# Bordnetzwandler.net
KiCad netlist of a schematic drawn in EAGLE
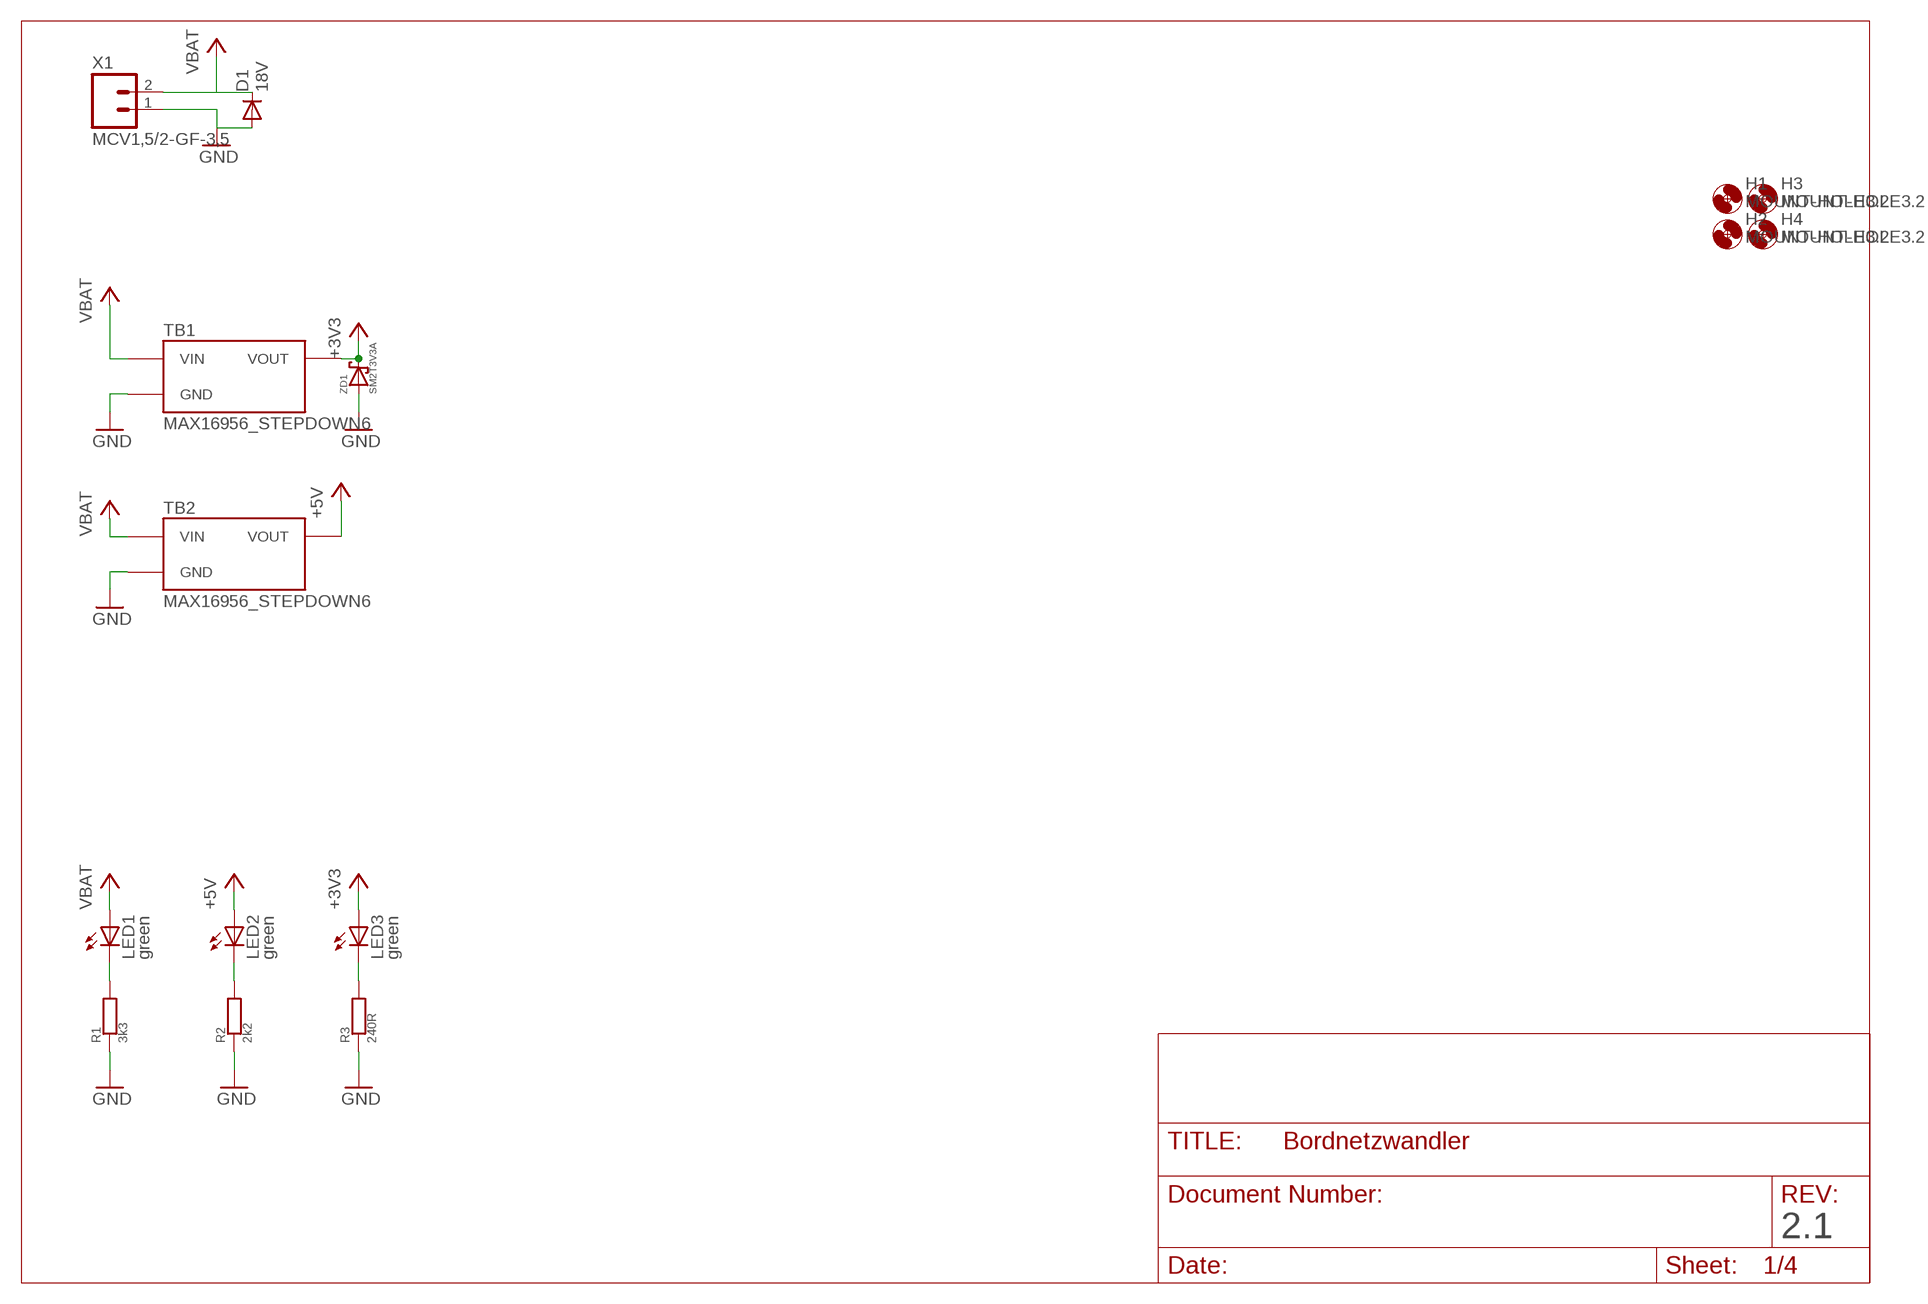
[diagram p0: schematic, sheet 1]
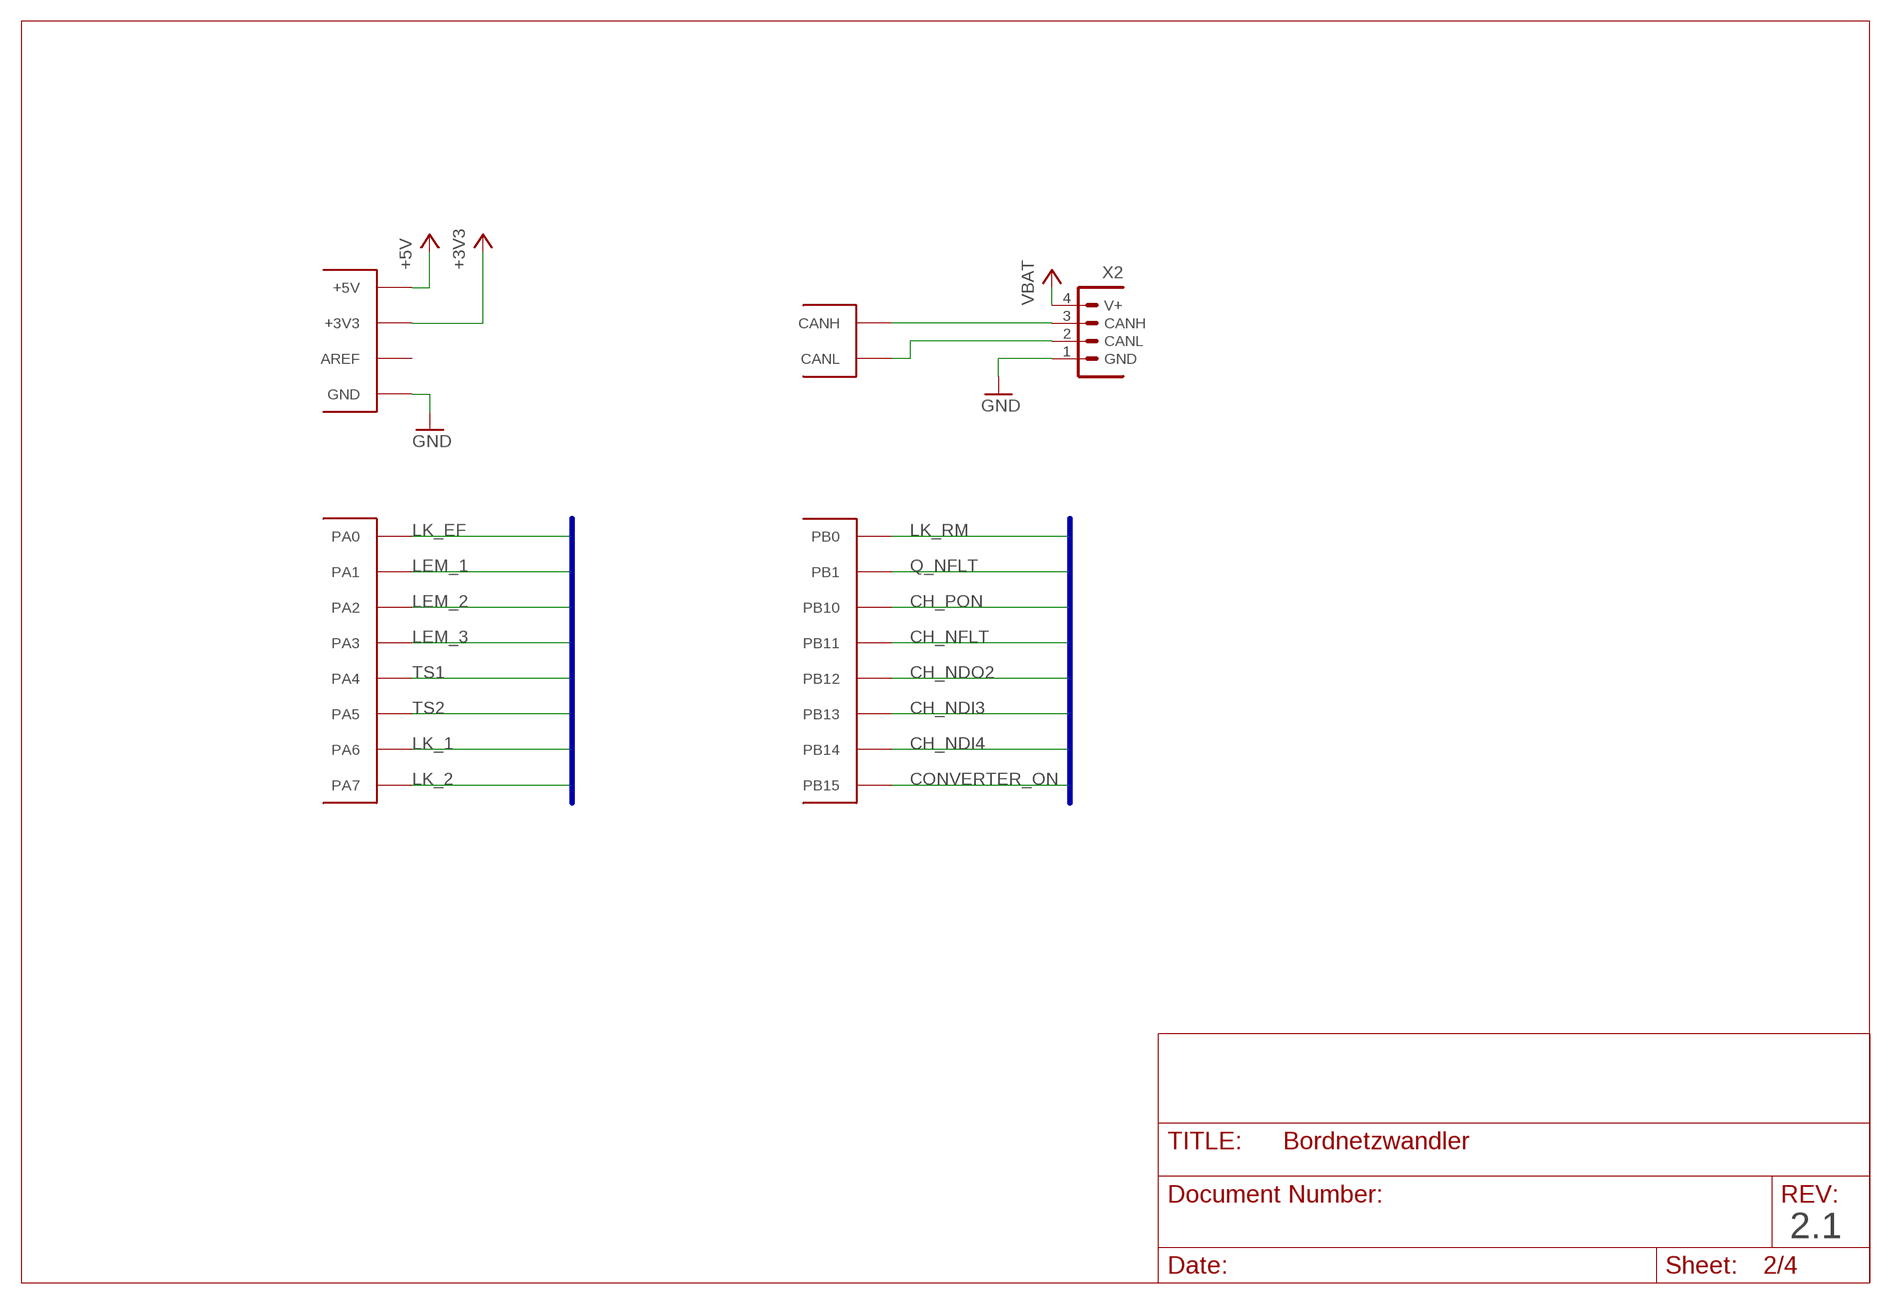
[diagram p1: schematic, sheet 2]
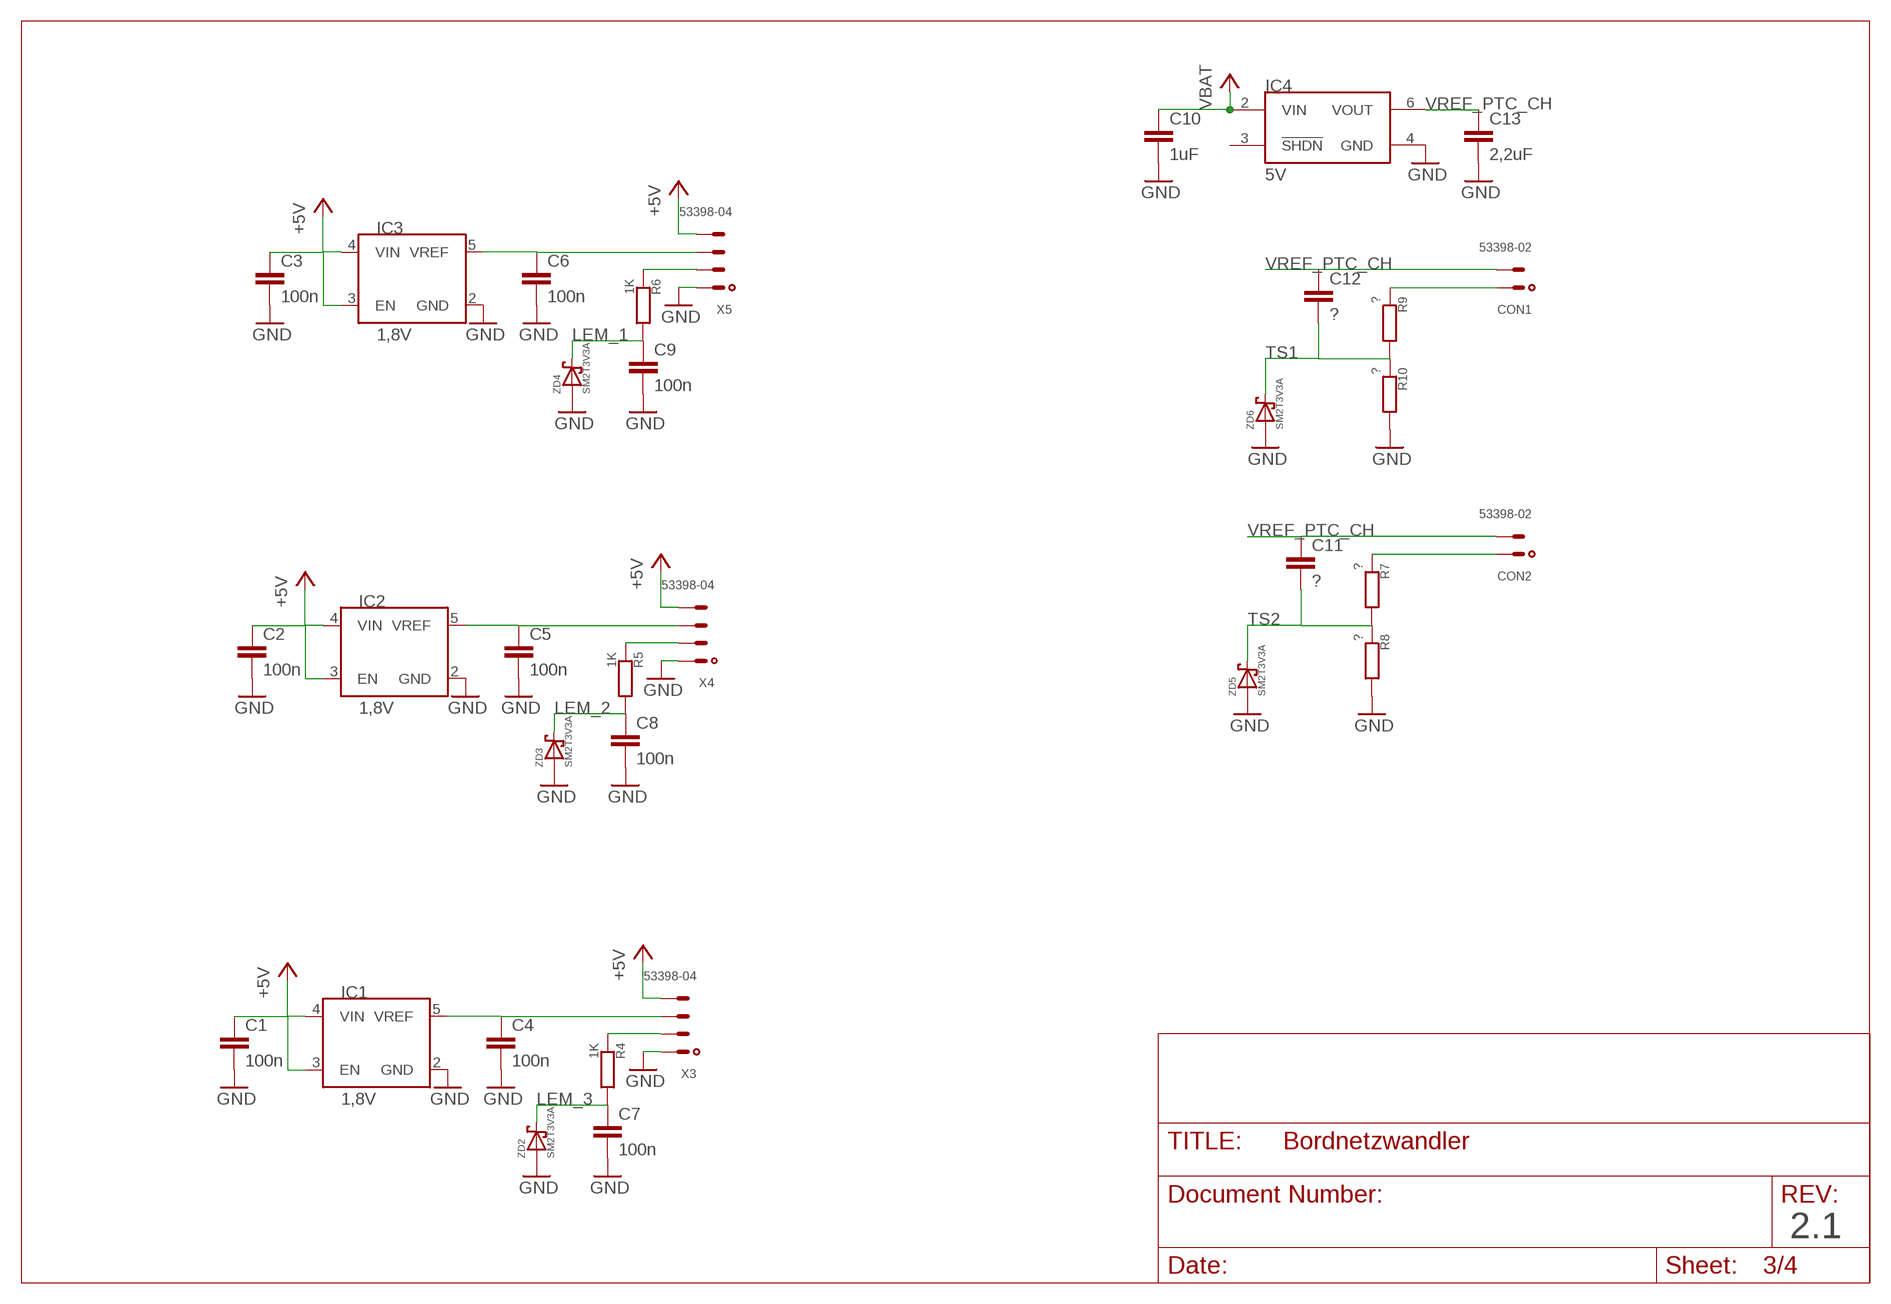
[diagram p2: schematic, sheet 3]
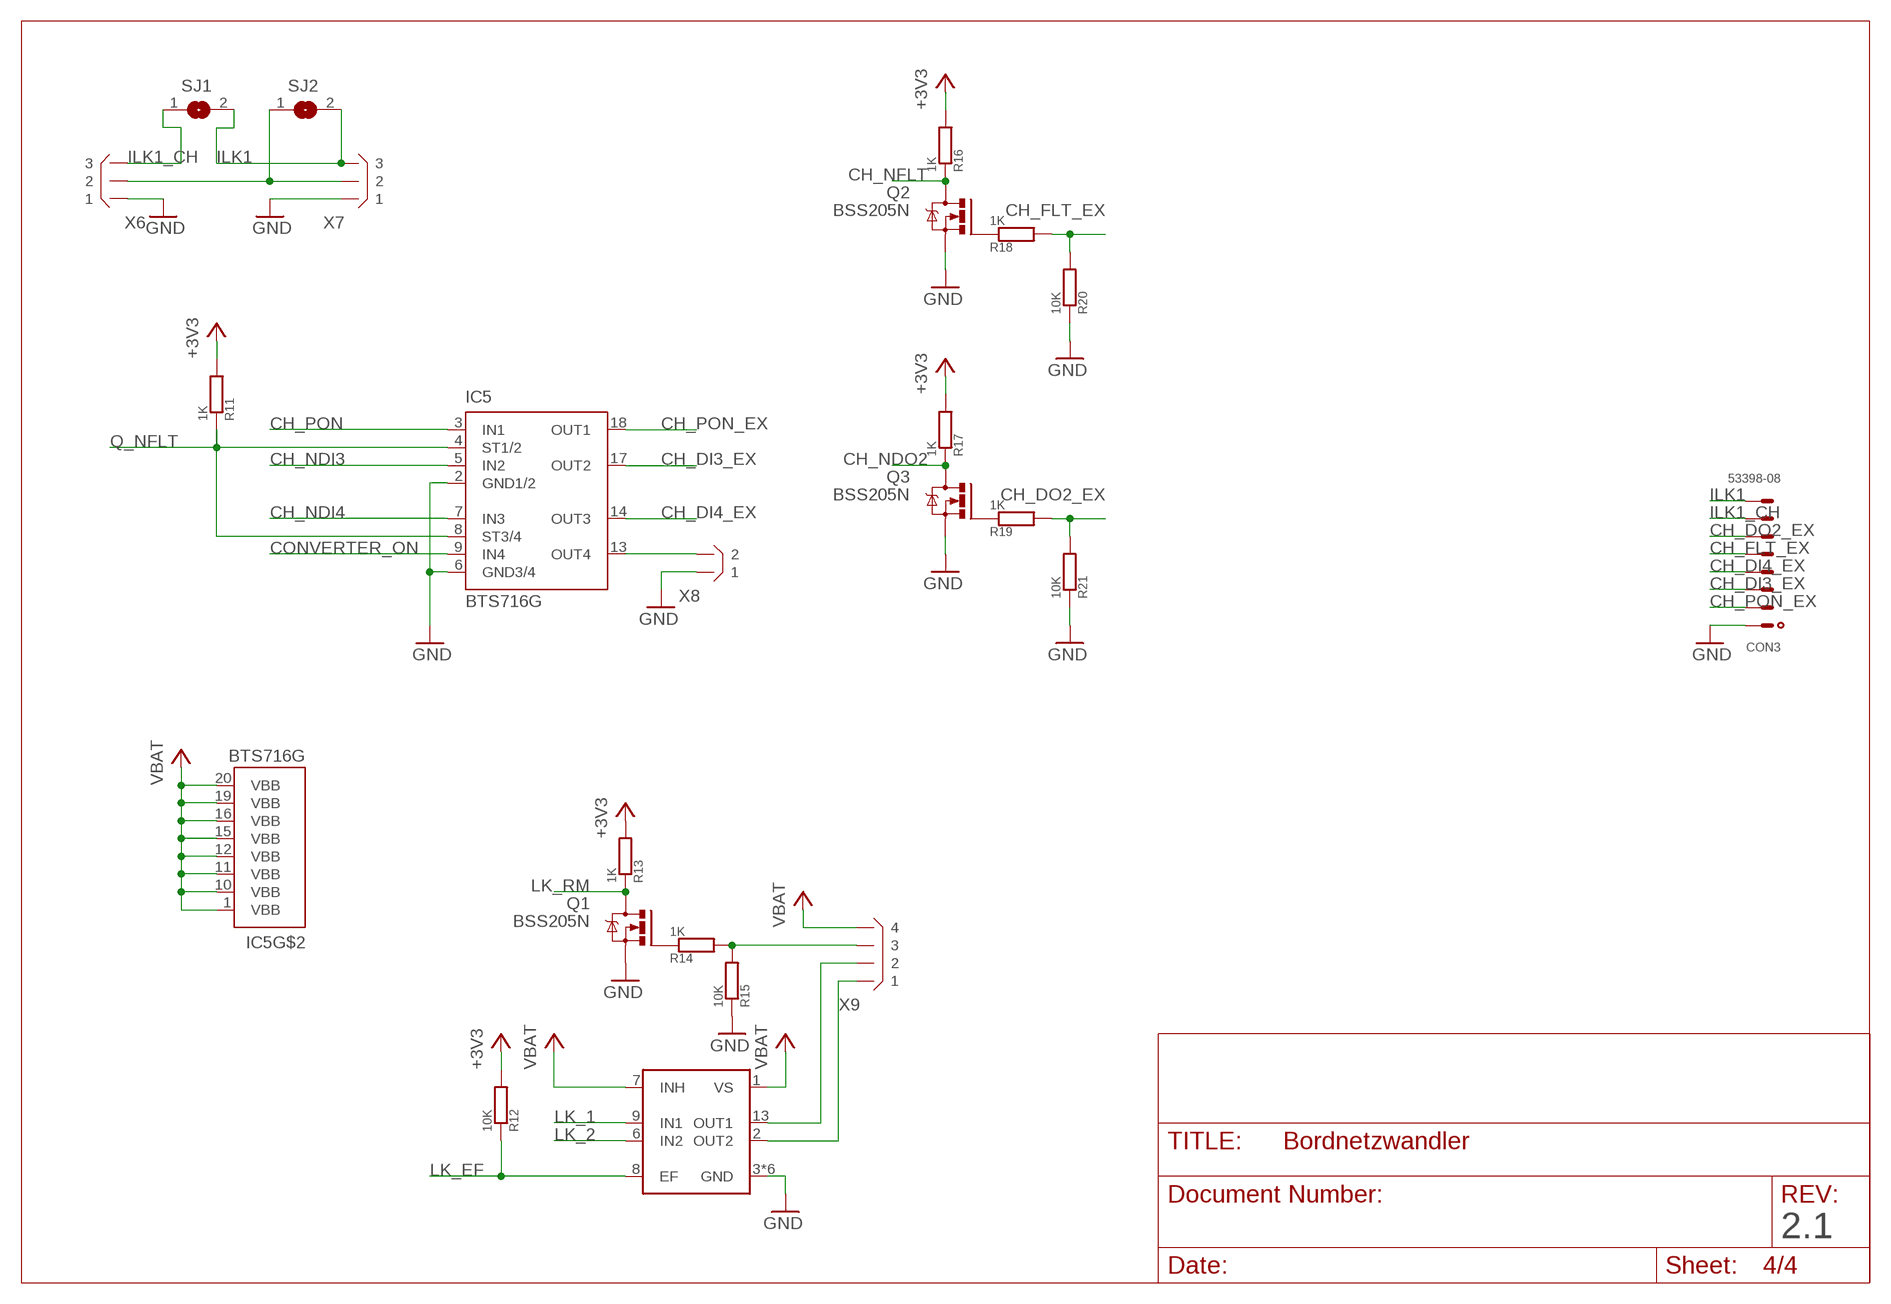
[diagram p3: schematic, sheet 4]

(export (version "E")
  (design (tool "Eeschema 10.0.6"))
  (components
    (comp (ref "D1")
      (value "18V")
      (footprint "eagle-import:DO214AA")
      (libsource (lib "eagle-import") (part "DIODE-DO214AA"))
    )
    (comp (ref "H1")
      (value "MOUNT-HOLE3.2")
      (footprint "eagle-import:3,2")
      (libsource (lib "eagle-import") (part "MOUNT-HOLE3.2"))
    )
    (comp (ref "H2")
      (value "MOUNT-HOLE3.2")
      (footprint "eagle-import:3,2")
      (libsource (lib "eagle-import") (part "MOUNT-HOLE3.2"))
    )
    (comp (ref "H3")
      (value "MOUNT-HOLE3.2")
      (footprint "eagle-import:3,2")
      (libsource (lib "eagle-import") (part "MOUNT-HOLE3.2"))
    )
    (comp (ref "H4")
      (value "MOUNT-HOLE3.2")
      (footprint "eagle-import:3,2")
      (libsource (lib "eagle-import") (part "MOUNT-HOLE3.2"))
    )
    (comp (ref "LED1")
      (value "green")
      (footprint "eagle-import:CHIP-LED0805")
      (libsource (lib "eagle-import") (part "LEDCHIP-LED0805"))
    )
    (comp (ref "LED2")
      (value "green")
      (footprint "eagle-import:CHIP-LED0805")
      (libsource (lib "eagle-import") (part "LEDCHIP-LED0805"))
    )
    (comp (ref "LED3")
      (value "green")
      (footprint "eagle-import:CHIP-LED0805")
      (libsource (lib "eagle-import") (part "LEDCHIP-LED0805"))
    )
    (comp (ref "R1")
      (value "3k3")
      (footprint "eagle-import:R0805")
      (libsource (lib "eagle-import") (part "R"))
    )
    (comp (ref "R2")
      (value "2k2")
      (footprint "eagle-import:R0805")
      (libsource (lib "eagle-import") (part "R"))
    )
    (comp (ref "R3")
      (value "240R")
      (footprint "eagle-import:R0805")
      (libsource (lib "eagle-import") (part "R"))
    )
    (comp (ref "TB1")
      (value "MAX16956_STEPDOWN6")
      (footprint "eagle-import:MAX16956_STEPDOWN6")
      (libsource (lib "eagle-import") (part "MAX16956_STEPDOWN6"))
    )
    (comp (ref "TB2")
      (value "MAX16956_STEPDOWN6")
      (footprint "eagle-import:MAX16956_STEPDOWN6")
      (libsource (lib "eagle-import") (part "MAX16956_STEPDOWN6"))
    )
    (comp (ref "X1")
      (value "MCV1,5/2-GF-3,5")
      (footprint "eagle-import:MCV1,5_2-GF-3,5")
      (libsource (lib "eagle-import") (part "MCV1,5/2-GF-3,5"))
    )
    (comp (ref "ZD1")
      (value "SM2T3V3A")
      (footprint "eagle-import:SM2T3V3A")
      (libsource (lib "eagle-import") (part "SM2T3V3A"))
    )
    (comp (ref "CON3")
      (value "53398-08")
      (footprint "eagle-import:53398-08")
      (libsource (lib "eagle-import") (part "53?-08398"))
    )
    (comp (ref "IC5")
      (value "BTS716G")
      (footprint "eagle-import:PG-DSO-20")
      (libsource (lib "eagle-import") (part "BTS716G"))
    )
    (comp (ref "IC6")
      (value "TLE4207GN")
      (footprint "eagle-import:INF-PG-DSO-14-22_N_1PRIMARY")
      (libsource (lib "eagle-import") (part "TLE4207GN"))
    )
    (comp (ref "Q1")
      (value "BSS205N")
      (footprint "eagle-import:SOT23")
      (libsource (lib "eagle-import") (part "BSS205N"))
    )
    (comp (ref "Q2")
      (value "BSS205N")
      (footprint "eagle-import:SOT23")
      (libsource (lib "eagle-import") (part "BSS205N"))
    )
    (comp (ref "Q3")
      (value "BSS205N")
      (footprint "eagle-import:SOT23")
      (libsource (lib "eagle-import") (part "BSS205N"))
    )
    (comp (ref "R11")
      (value "1K")
      (footprint "eagle-import:R0603")
      (libsource (lib "eagle-import") (part "R0603"))
    )
    (comp (ref "R12")
      (value "10K")
      (footprint "eagle-import:R0805")
      (libsource (lib "eagle-import") (part "R"))
    )
    (comp (ref "R13")
      (value "1K")
      (footprint "eagle-import:R0805")
      (libsource (lib "eagle-import") (part "R"))
    )
    (comp (ref "R14")
      (value "1K")
      (footprint "eagle-import:R0805")
      (libsource (lib "eagle-import") (part "R"))
    )
    (comp (ref "R15")
      (value "10K")
      (footprint "eagle-import:R0805")
      (libsource (lib "eagle-import") (part "R"))
    )
    (comp (ref "R16")
      (value "1K")
      (footprint "eagle-import:R0603")
      (libsource (lib "eagle-import") (part "R0603"))
    )
    (comp (ref "R17")
      (value "1K")
      (footprint "eagle-import:R0603")
      (libsource (lib "eagle-import") (part "R0603"))
    )
    (comp (ref "R18")
      (value "1K")
      (footprint "eagle-import:R0603")
      (libsource (lib "eagle-import") (part "R0603"))
    )
    (comp (ref "R19")
      (value "1K")
      (footprint "eagle-import:R0603")
      (libsource (lib "eagle-import") (part "R0603"))
    )
    (comp (ref "R20")
      (value "10K")
      (footprint "eagle-import:R0603")
      (libsource (lib "eagle-import") (part "R0603"))
    )
    (comp (ref "R21")
      (value "10K")
      (footprint "eagle-import:R0603")
      (libsource (lib "eagle-import") (part "R0603"))
    )
    (comp (ref "SJ1") (value "SJ") (footprint "eagle-import:SJ") (libsource (lib "eagle-import") (part "SJ")))
    (comp (ref "SJ2") (value "SJ") (footprint "eagle-import:SJ") (libsource (lib "eagle-import") (part "SJ")))
    (comp (ref "X6")
      (value "B3B-XH")
      (footprint "eagle-import:B3B-XH")
      (libsource (lib "eagle-import") (part "?3B-XHB"))
    )
    (comp (ref "X7")
      (value "B3B-XH")
      (footprint "eagle-import:B3B-XH")
      (libsource (lib "eagle-import") (part "?3B-XHB"))
    )
    (comp (ref "X8")
      (value "B2B-XH")
      (footprint "eagle-import:B2B-XH")
      (libsource (lib "eagle-import") (part "?2B-XHB"))
    )
    (comp (ref "X9")
      (value "B4B-XH")
      (footprint "eagle-import:B4B-XH")
      (libsource (lib "eagle-import") (part "?4B-XHB"))
    )
    (comp (ref "CANIO_1")
      (value "STM32F103XX_CAN-IO-EXPANDER")
      (footprint "eagle-import:STM32F103XX_CANIO-EXPANDER")
      (libsource (lib "eagle-import") (part "STM32F103XX_CAN-IO-EXPANDER"))
    )
    (comp (ref "X2")
      (value "CIOC_4-1-FV-A_CAN-BELEGUNG")
      (footprint "eagle-import:CIOC_4-1-FV")
      (libsource (lib "eagle-import") (part "CIOC_4-1-FV-A_CAN-BELEGUNG"))
    )
    (comp (ref "C1")
      (value "100n")
      (footprint "eagle-import:C0805")
      (libsource (lib "eagle-import") (part "C-EUC0805"))
    )
    (comp (ref "C2")
      (value "100n")
      (footprint "eagle-import:C0805")
      (libsource (lib "eagle-import") (part "C-EUC0805"))
    )
    (comp (ref "C3")
      (value "100n")
      (footprint "eagle-import:C0805")
      (libsource (lib "eagle-import") (part "C-EUC0805"))
    )
    (comp (ref "C4")
      (value "100n")
      (footprint "eagle-import:C0805")
      (libsource (lib "eagle-import") (part "C-EUC0805"))
    )
    (comp (ref "C5")
      (value "100n")
      (footprint "eagle-import:C0805")
      (libsource (lib "eagle-import") (part "C-EUC0805"))
    )
    (comp (ref "C6")
      (value "100n")
      (footprint "eagle-import:C0805")
      (libsource (lib "eagle-import") (part "C-EUC0805"))
    )
    (comp (ref "C7")
      (value "100n")
      (footprint "eagle-import:C0805")
      (libsource (lib "eagle-import") (part "C-EUC0805"))
    )
    (comp (ref "C8")
      (value "100n")
      (footprint "eagle-import:C0805")
      (libsource (lib "eagle-import") (part "C-EUC0805"))
    )
    (comp (ref "C9")
      (value "100n")
      (footprint "eagle-import:C0805")
      (libsource (lib "eagle-import") (part "C-EUC0805"))
    )
    (comp (ref "C10")
      (value "1uF")
      (footprint "eagle-import:C0805")
      (libsource (lib "eagle-import") (part "C-EUC0805"))
    )
    (comp (ref "C11")
      (value "?")
      (footprint "eagle-import:C0805")
      (libsource (lib "eagle-import") (part "C-EUC0805"))
    )
    (comp (ref "C12")
      (value "?")
      (footprint "eagle-import:C0805")
      (libsource (lib "eagle-import") (part "C-EUC0805"))
    )
    (comp (ref "C13")
      (value "2,2uF")
      (footprint "eagle-import:C0805")
      (libsource (lib "eagle-import") (part "C-EUC0805"))
    )
    (comp (ref "CON1")
      (value "53398-02")
      (footprint "eagle-import:53398-02")
      (libsource (lib "eagle-import") (part "53?-02398"))
    )
    (comp (ref "CON2")
      (value "53398-02")
      (footprint "eagle-import:53398-02")
      (libsource (lib "eagle-import") (part "53?-02398"))
    )
    (comp (ref "IC1")
      (value "1,8V")
      (footprint "eagle-import:SOT23-5L")
      (libsource (lib "eagle-import") (part "LM4132L"))
    )
    (comp (ref "IC2")
      (value "1,8V")
      (footprint "eagle-import:SOT23-5L")
      (libsource (lib "eagle-import") (part "LM4132L"))
    )
    (comp (ref "IC3")
      (value "1,8V")
      (footprint "eagle-import:SOT23-5L")
      (libsource (lib "eagle-import") (part "LM4132L"))
    )
    (comp (ref "IC4")
      (value "5V")
      (footprint "eagle-import:SO08")
      (libsource (lib "eagle-import") (part "LT1461"))
    )
    (comp (ref "R4")
      (value "1K")
      (footprint "eagle-import:R0805")
      (libsource (lib "eagle-import") (part "R"))
    )
    (comp (ref "R5")
      (value "1K")
      (footprint "eagle-import:R0805")
      (libsource (lib "eagle-import") (part "R"))
    )
    (comp (ref "R6")
      (value "1K")
      (footprint "eagle-import:R0805")
      (libsource (lib "eagle-import") (part "R"))
    )
    (comp (ref "R7") (value "?") (footprint "eagle-import:R0805") (libsource (lib "eagle-import") (part "R")))
    (comp (ref "R8") (value "?") (footprint "eagle-import:R0805") (libsource (lib "eagle-import") (part "R")))
    (comp (ref "R9") (value "?") (footprint "eagle-import:R0805") (libsource (lib "eagle-import") (part "R")))
    (comp (ref "R10")
      (value "?")
      (footprint "eagle-import:R0805")
      (libsource (lib "eagle-import") (part "R"))
    )
    (comp (ref "X3")
      (value "53398-04")
      (footprint "eagle-import:53398-04")
      (libsource (lib "eagle-import") (part "53?-04398"))
    )
    (comp (ref "X4")
      (value "53398-04")
      (footprint "eagle-import:53398-04")
      (libsource (lib "eagle-import") (part "53?-04398"))
    )
    (comp (ref "X5")
      (value "53398-04")
      (footprint "eagle-import:53398-04")
      (libsource (lib "eagle-import") (part "53?-04398"))
    )
    (comp (ref "ZD2")
      (value "SM2T3V3A")
      (footprint "eagle-import:SM2T3V3A")
      (libsource (lib "eagle-import") (part "SM2T3V3A"))
    )
    (comp (ref "ZD3")
      (value "SM2T3V3A")
      (footprint "eagle-import:SM2T3V3A")
      (libsource (lib "eagle-import") (part "SM2T3V3A"))
    )
    (comp (ref "ZD4")
      (value "SM2T3V3A")
      (footprint "eagle-import:SM2T3V3A")
      (libsource (lib "eagle-import") (part "SM2T3V3A"))
    )
    (comp (ref "ZD5")
      (value "SM2T3V3A")
      (footprint "eagle-import:SM2T3V3A")
      (libsource (lib "eagle-import") (part "SM2T3V3A"))
    )
    (comp (ref "ZD6")
      (value "SM2T3V3A")
      (footprint "eagle-import:SM2T3V3A")
      (libsource (lib "eagle-import") (part "SM2T3V3A"))
    )
  )
  (nets
    (net (code "1") (name "+3V3") (class "Default")
      (node (ref "CANIO_1") (pin "VCC") (pinfunction "+3V3_VCC") (pintype "power_in"))
      (node (ref "LED3") (pin "A") (pinfunction "A_A") (pintype "passive"))
      (node (ref "R11") (pin "2") (pinfunction "2_2") (pintype "passive"))
      (node (ref "R12") (pin "2") (pinfunction "2_2") (pintype "passive"))
      (node (ref "R13") (pin "2") (pinfunction "2_2") (pintype "passive"))
      (node (ref "R16") (pin "2") (pinfunction "2_2") (pintype "passive"))
      (node (ref "R17") (pin "2") (pinfunction "2_2") (pintype "passive"))
      (node (ref "TB1") (pin "VOUT") (pinfunction "VOUT_VOUT") (pintype "passive"))
      (node (ref "ZD1") (pin "P$2") (pinfunction "P$2_P$2") (pintype "bidirectional"))
    )
    (net (code "2") (name "+5V") (class "Default")
      (node (ref "C1") (pin "1") (pinfunction "1_1") (pintype "passive"))
      (node (ref "C2") (pin "1") (pinfunction "1_1") (pintype "passive"))
      (node (ref "C3") (pin "1") (pinfunction "1_1") (pintype "passive"))
      (node (ref "CANIO_1") (pin "+5V") (pinfunction "+5V_+5V") (pintype "power_in"))
      (node (ref "IC1") (pin "3") (pinfunction "EN_3") (pintype "bidirectional"))
      (node (ref "IC1") (pin "4") (pinfunction "VIN_4") (pintype "bidirectional"))
      (node (ref "IC2") (pin "3") (pinfunction "EN_3") (pintype "bidirectional"))
      (node (ref "IC2") (pin "4") (pinfunction "VIN_4") (pintype "bidirectional"))
      (node (ref "IC3") (pin "3") (pinfunction "EN_3") (pintype "bidirectional"))
      (node (ref "IC3") (pin "4") (pinfunction "VIN_4") (pintype "bidirectional"))
      (node (ref "LED2") (pin "A") (pinfunction "A_A") (pintype "passive"))
      (node (ref "TB2") (pin "VOUT") (pinfunction "VOUT_VOUT") (pintype "passive"))
      (node (ref "X3") (pin "4") (pinfunction "4_4") (pintype "passive"))
      (node (ref "X4") (pin "4") (pinfunction "4_4") (pintype "passive"))
      (node (ref "X5") (pin "4") (pinfunction "4_4") (pintype "passive"))
    )
    (net (code "3") (name "CH_DI3_EX") (class "Default")
      (node (ref "CON3") (pin "3") (pinfunction "3_3") (pintype "passive"))
      (node (ref "IC5") (pin "17") (pinfunction "OUT2_17") (pintype "output"))
    )
    (net (code "4") (name "CH_DI4_EX") (class "Default")
      (node (ref "CON3") (pin "4") (pinfunction "4_4") (pintype "passive"))
      (node (ref "IC5") (pin "14") (pinfunction "OUT3_14") (pintype "output"))
    )
    (net (code "5") (name "CH_DO2_EX") (class "Default")
      (node (ref "CON3") (pin "6") (pinfunction "6_6") (pintype "passive"))
      (node (ref "R19") (pin "2") (pinfunction "2_2") (pintype "passive"))
      (node (ref "R21") (pin "2") (pinfunction "2_2") (pintype "passive"))
    )
    (net (code "6") (name "CH_FLT_EX") (class "Default")
      (node (ref "CON3") (pin "5") (pinfunction "5_5") (pintype "passive"))
      (node (ref "R18") (pin "2") (pinfunction "2_2") (pintype "passive"))
      (node (ref "R20") (pin "2") (pinfunction "2_2") (pintype "passive"))
    )
    (net (code "7") (name "CH_NDI3") (class "Default")
      (node (ref "CANIO_1") (pin "PB13") (pinfunction "PB13_PB13") (pintype "bidirectional"))
      (node (ref "IC5") (pin "5") (pinfunction "IN2_5") (pintype "input"))
    )
    (net (code "8") (name "CH_NDI4") (class "Default")
      (node (ref "CANIO_1") (pin "PB14") (pinfunction "PB14_PB14") (pintype "bidirectional"))
      (node (ref "IC5") (pin "7") (pinfunction "IN3_7") (pintype "input"))
    )
    (net (code "9") (name "CH_NDO2") (class "Default")
      (node (ref "CANIO_1") (pin "PB12") (pinfunction "PB12_PB12") (pintype "bidirectional"))
      (node (ref "Q3") (pin "3") (pinfunction "D_3") (pintype "passive"))
      (node (ref "R17") (pin "1") (pinfunction "1_1") (pintype "passive"))
    )
    (net (code "10") (name "CH_NFLT") (class "Default")
      (node (ref "CANIO_1") (pin "PB11") (pinfunction "PB11_PB11") (pintype "bidirectional"))
      (node (ref "Q2") (pin "3") (pinfunction "D_3") (pintype "passive"))
      (node (ref "R16") (pin "1") (pinfunction "1_1") (pintype "passive"))
    )
    (net (code "11") (name "CH_PON") (class "Default")
      (node (ref "CANIO_1") (pin "PB10") (pinfunction "PB10_PB10") (pintype "bidirectional"))
      (node (ref "IC5") (pin "3") (pinfunction "IN1_3") (pintype "input"))
    )
    (net (code "12") (name "CH_PON_EX") (class "Default")
      (node (ref "CON3") (pin "2") (pinfunction "2_2") (pintype "passive"))
      (node (ref "IC5") (pin "18") (pinfunction "OUT1_18") (pintype "output"))
    )
    (net (code "13") (name "CONVERTER_ON") (class "Default")
      (node (ref "CANIO_1") (pin "PB15") (pinfunction "PB15_PB15") (pintype "bidirectional"))
      (node (ref "IC5") (pin "9") (pinfunction "IN4_9") (pintype "input"))
    )
    (net (code "14") (name "GND") (class "Default")
      (node (ref "C1") (pin "2") (pinfunction "2_2") (pintype "passive"))
      (node (ref "C10") (pin "2") (pinfunction "2_2") (pintype "passive"))
      (node (ref "C13") (pin "2") (pinfunction "2_2") (pintype "passive"))
      (node (ref "C2") (pin "2") (pinfunction "2_2") (pintype "passive"))
      (node (ref "C3") (pin "2") (pinfunction "2_2") (pintype "passive"))
      (node (ref "C4") (pin "2") (pinfunction "2_2") (pintype "passive"))
      (node (ref "C5") (pin "2") (pinfunction "2_2") (pintype "passive"))
      (node (ref "C6") (pin "2") (pinfunction "2_2") (pintype "passive"))
      (node (ref "C7") (pin "2") (pinfunction "2_2") (pintype "passive"))
      (node (ref "C8") (pin "2") (pinfunction "2_2") (pintype "passive"))
      (node (ref "C9") (pin "2") (pinfunction "2_2") (pintype "passive"))
      (node (ref "CANIO_1") (pin "GND1") (pinfunction "GND_GND1") (pintype "power_in"))
      (node (ref "CON3") (pin "1") (pinfunction "1_1") (pintype "passive"))
      (node (ref "D1") (pin "A") (pinfunction "A_A") (pintype "passive"))
      (node (ref "IC1") (pin "2") (pinfunction "GND_2") (pintype "bidirectional"))
      (node (ref "IC2") (pin "2") (pinfunction "GND_2") (pintype "bidirectional"))
      (node (ref "IC3") (pin "2") (pinfunction "GND_2") (pintype "bidirectional"))
      (node (ref "IC4") (pin "4") (pinfunction "GND_4") (pintype "power_in"))
      (node (ref "IC5") (pin "2") (pinfunction "GND1/2_2") (pintype "input"))
      (node (ref "IC5") (pin "6") (pinfunction "GND3/4_6") (pintype "input"))
      (node (ref "IC6") (pin "10") (pinfunction "GND_10") (pintype "bidirectional"))
      (node (ref "IC6") (pin "11") (pinfunction "GND_11") (pintype "bidirectional"))
      (node (ref "IC6") (pin "12") (pinfunction "GND_12") (pintype "bidirectional"))
      (node (ref "IC6") (pin "3") (pinfunction "GND_3") (pintype "bidirectional"))
      (node (ref "IC6") (pin "4") (pinfunction "GND_4") (pintype "bidirectional"))
      (node (ref "IC6") (pin "5") (pinfunction "GND_5") (pintype "bidirectional"))
      (node (ref "Q1") (pin "2") (pinfunction "S_2") (pintype "passive"))
      (node (ref "Q2") (pin "2") (pinfunction "S_2") (pintype "passive"))
      (node (ref "Q3") (pin "2") (pinfunction "S_2") (pintype "passive"))
      (node (ref "R1") (pin "1") (pinfunction "1_1") (pintype "passive"))
      (node (ref "R10") (pin "2") (pinfunction "2_2") (pintype "passive"))
      (node (ref "R15") (pin "1") (pinfunction "1_1") (pintype "passive"))
      (node (ref "R2") (pin "1") (pinfunction "1_1") (pintype "passive"))
      (node (ref "R20") (pin "1") (pinfunction "1_1") (pintype "passive"))
      (node (ref "R21") (pin "1") (pinfunction "1_1") (pintype "passive"))
      (node (ref "R3") (pin "1") (pinfunction "1_1") (pintype "passive"))
      (node (ref "R8") (pin "2") (pinfunction "2_2") (pintype "passive"))
      (node (ref "TB1") (pin "GND") (pinfunction "GND_GND") (pintype "power_in"))
      (node (ref "TB1") (pin "GND2") (pinfunction "GND_GND2") (pintype "power_in"))
      (node (ref "TB2") (pin "GND") (pinfunction "GND_GND") (pintype "power_in"))
      (node (ref "TB2") (pin "GND2") (pinfunction "GND_GND2") (pintype "power_in"))
      (node (ref "X1") (pin "1") (pinfunction "1_1") (pintype "passive"))
      (node (ref "X2") (pin "1") (pinfunction "GND_1") (pintype "passive"))
      (node (ref "X3") (pin "1") (pinfunction "1_1") (pintype "passive"))
      (node (ref "X4") (pin "1") (pinfunction "1_1") (pintype "passive"))
      (node (ref "X5") (pin "1") (pinfunction "1_1") (pintype "passive"))
      (node (ref "X6") (pin "P$1") (pinfunction "1_P$1") (pintype "bidirectional"))
      (node (ref "X7") (pin "P$1") (pinfunction "1_P$1") (pintype "bidirectional"))
      (node (ref "X8") (pin "P$1") (pinfunction "1_P$1") (pintype "bidirectional"))
      (node (ref "ZD1") (pin "P$1") (pinfunction "P$1_P$1") (pintype "bidirectional"))
      (node (ref "ZD1") (pin "P$11") (pinfunction "P$1_P$11") (pintype "bidirectional"))
      (node (ref "ZD2") (pin "P$1") (pinfunction "P$1_P$1") (pintype "bidirectional"))
      (node (ref "ZD2") (pin "P$11") (pinfunction "P$1_P$11") (pintype "bidirectional"))
      (node (ref "ZD3") (pin "P$1") (pinfunction "P$1_P$1") (pintype "bidirectional"))
      (node (ref "ZD3") (pin "P$11") (pinfunction "P$1_P$11") (pintype "bidirectional"))
      (node (ref "ZD4") (pin "P$1") (pinfunction "P$1_P$1") (pintype "bidirectional"))
      (node (ref "ZD4") (pin "P$11") (pinfunction "P$1_P$11") (pintype "bidirectional"))
      (node (ref "ZD5") (pin "P$1") (pinfunction "P$1_P$1") (pintype "bidirectional"))
      (node (ref "ZD5") (pin "P$11") (pinfunction "P$1_P$11") (pintype "bidirectional"))
      (node (ref "ZD6") (pin "P$1") (pinfunction "P$1_P$1") (pintype "bidirectional"))
      (node (ref "ZD6") (pin "P$11") (pinfunction "P$1_P$11") (pintype "bidirectional"))
    )
    (net (code "15") (name "ILK1") (class "Default")
      (node (ref "CON3") (pin "8") (pinfunction "8_8") (pintype "passive"))
      (node (ref "SJ1") (pin "2") (pinfunction "2_2") (pintype "passive"))
      (node (ref "SJ2") (pin "2") (pinfunction "2_2") (pintype "passive"))
      (node (ref "X7") (pin "P$3") (pinfunction "3_P$3") (pintype "bidirectional"))
    )
    (net (code "16") (name "ILK1_CH") (class "Default")
      (node (ref "CON3") (pin "7") (pinfunction "7_7") (pintype "passive"))
      (node (ref "SJ1") (pin "1") (pinfunction "1_1") (pintype "passive"))
      (node (ref "X6") (pin "P$3") (pinfunction "3_P$3") (pintype "bidirectional"))
    )
    (net (code "17") (name "LEM_1") (class "Default")
      (node (ref "C9") (pin "1") (pinfunction "1_1") (pintype "passive"))
      (node (ref "CANIO_1") (pin "PA1") (pinfunction "PA1_PA1") (pintype "bidirectional"))
      (node (ref "R6") (pin "2") (pinfunction "2_2") (pintype "passive"))
      (node (ref "ZD4") (pin "P$2") (pinfunction "P$2_P$2") (pintype "bidirectional"))
    )
    (net (code "18") (name "LEM_2") (class "Default")
      (node (ref "C8") (pin "1") (pinfunction "1_1") (pintype "passive"))
      (node (ref "CANIO_1") (pin "PA2") (pinfunction "PA2_PA2") (pintype "bidirectional"))
      (node (ref "R5") (pin "2") (pinfunction "2_2") (pintype "passive"))
      (node (ref "ZD3") (pin "P$2") (pinfunction "P$2_P$2") (pintype "bidirectional"))
    )
    (net (code "19") (name "LEM_3") (class "Default")
      (node (ref "C7") (pin "1") (pinfunction "1_1") (pintype "passive"))
      (node (ref "CANIO_1") (pin "PA3") (pinfunction "PA3_PA3") (pintype "bidirectional"))
      (node (ref "R4") (pin "2") (pinfunction "2_2") (pintype "passive"))
      (node (ref "ZD2") (pin "P$2") (pinfunction "P$2_P$2") (pintype "bidirectional"))
    )
    (net (code "20") (name "LK_1") (class "Default")
      (node (ref "CANIO_1") (pin "PA6") (pinfunction "PA6_PA6") (pintype "bidirectional"))
      (node (ref "IC6") (pin "9") (pinfunction "IN1_9") (pintype "bidirectional"))
    )
    (net (code "21") (name "LK_2") (class "Default")
      (node (ref "CANIO_1") (pin "PA7") (pinfunction "PA7_PA7") (pintype "bidirectional"))
      (node (ref "IC6") (pin "6") (pinfunction "IN2_6") (pintype "bidirectional"))
    )
    (net (code "22") (name "LK_EF") (class "Default")
      (node (ref "CANIO_1") (pin "PA0") (pinfunction "PA0_PA0") (pintype "bidirectional"))
      (node (ref "IC6") (pin "8") (pinfunction "EF_8") (pintype "bidirectional"))
      (node (ref "R12") (pin "1") (pinfunction "1_1") (pintype "passive"))
    )
    (net (code "23") (name "LK_RM") (class "Default")
      (node (ref "CANIO_1") (pin "PB0") (pinfunction "PB0_PB0") (pintype "bidirectional"))
      (node (ref "Q1") (pin "3") (pinfunction "D_3") (pintype "passive"))
      (node (ref "R13") (pin "1") (pinfunction "1_1") (pintype "passive"))
    )
    (net (code "24") (name "Net-(CON1-Pad1)") (class "Default")
      (node (ref "CON1") (pin "1") (pinfunction "1_1") (pintype "passive"))
      (node (ref "R9") (pin "1") (pinfunction "1_1") (pintype "passive"))
    )
    (net (code "25") (name "Net-(CON2-Pad1)") (class "Default")
      (node (ref "CON2") (pin "1") (pinfunction "1_1") (pintype "passive"))
      (node (ref "R7") (pin "1") (pinfunction "1_1") (pintype "passive"))
    )
    (net (code "26") (name "Net-(IC1-VREF)") (class "Default")
      (node (ref "C4") (pin "1") (pinfunction "1_1") (pintype "passive"))
      (node (ref "IC1") (pin "5") (pinfunction "VREF_5") (pintype "bidirectional"))
      (node (ref "X3") (pin "3") (pinfunction "3_3") (pintype "passive"))
    )
    (net (code "27") (name "Net-(IC2-VREF)") (class "Default")
      (node (ref "C5") (pin "1") (pinfunction "1_1") (pintype "passive"))
      (node (ref "IC2") (pin "5") (pinfunction "VREF_5") (pintype "bidirectional"))
      (node (ref "X4") (pin "3") (pinfunction "3_3") (pintype "passive"))
    )
    (net (code "28") (name "Net-(IC3-VREF)") (class "Default")
      (node (ref "C6") (pin "1") (pinfunction "1_1") (pintype "passive"))
      (node (ref "IC3") (pin "5") (pinfunction "VREF_5") (pintype "bidirectional"))
      (node (ref "X5") (pin "3") (pinfunction "3_3") (pintype "passive"))
    )
    (net (code "29") (name "Net-(IC5A-OUT4)") (class "Default")
      (node (ref "IC5") (pin "13") (pinfunction "OUT4_13") (pintype "output"))
      (node (ref "X8") (pin "P$2") (pinfunction "2_P$2") (pintype "bidirectional"))
    )
    (net (code "30") (name "Net-(IC6-OUT1)") (class "Default")
      (node (ref "IC6") (pin "13") (pinfunction "OUT1_13") (pintype "bidirectional"))
      (node (ref "X9") (pin "P$2") (pinfunction "2_P$2") (pintype "bidirectional"))
    )
    (net (code "31") (name "Net-(IC6-OUT2)") (class "Default")
      (node (ref "IC6") (pin "2") (pinfunction "OUT2_2") (pintype "bidirectional"))
      (node (ref "X9") (pin "P$1") (pinfunction "1_P$1") (pintype "bidirectional"))
    )
    (net (code "32") (name "Net-(LED1-PadC)") (class "Default")
      (node (ref "LED1") (pin "C") (pinfunction "C_C") (pintype "passive"))
      (node (ref "R1") (pin "2") (pinfunction "2_2") (pintype "passive"))
    )
    (net (code "33") (name "Net-(LED2-PadC)") (class "Default")
      (node (ref "LED2") (pin "C") (pinfunction "C_C") (pintype "passive"))
      (node (ref "R2") (pin "2") (pinfunction "2_2") (pintype "passive"))
    )
    (net (code "34") (name "Net-(LED3-PadC)") (class "Default")
      (node (ref "LED3") (pin "C") (pinfunction "C_C") (pintype "passive"))
      (node (ref "R3") (pin "2") (pinfunction "2_2") (pintype "passive"))
    )
    (net (code "35") (name "Net-(Q1-G)") (class "Default")
      (node (ref "Q1") (pin "1") (pinfunction "G_1") (pintype "passive"))
      (node (ref "R14") (pin "1") (pinfunction "1_1") (pintype "passive"))
    )
    (net (code "36") (name "Net-(Q2-G)") (class "Default")
      (node (ref "Q2") (pin "1") (pinfunction "G_1") (pintype "passive"))
      (node (ref "R18") (pin "1") (pinfunction "1_1") (pintype "passive"))
    )
    (net (code "37") (name "Net-(Q3-G)") (class "Default")
      (node (ref "Q3") (pin "1") (pinfunction "G_1") (pintype "passive"))
      (node (ref "R19") (pin "1") (pinfunction "1_1") (pintype "passive"))
    )
    (net (code "38") (name "Net-(R4-Pad1)") (class "Default")
      (node (ref "R4") (pin "1") (pinfunction "1_1") (pintype "passive"))
      (node (ref "X3") (pin "2") (pinfunction "2_2") (pintype "passive"))
    )
    (net (code "39") (name "Net-(R5-Pad1)") (class "Default")
      (node (ref "R5") (pin "1") (pinfunction "1_1") (pintype "passive"))
      (node (ref "X4") (pin "2") (pinfunction "2_2") (pintype "passive"))
    )
    (net (code "40") (name "Net-(R6-Pad1)") (class "Default")
      (node (ref "R6") (pin "1") (pinfunction "1_1") (pintype "passive"))
      (node (ref "X5") (pin "2") (pinfunction "2_2") (pintype "passive"))
    )
    (net (code "41") (name "Net-(X2-CANH)") (class "Default")
      (node (ref "CANIO_1") (pin "CANH") (pinfunction "CANH_CANH") (pintype "bidirectional"))
      (node (ref "X2") (pin "3") (pinfunction "CANH_3") (pintype "passive"))
    )
    (net (code "42") (name "Net-(X2-CANL)") (class "Default")
      (node (ref "CANIO_1") (pin "CANL") (pinfunction "CANL_CANL") (pintype "bidirectional"))
      (node (ref "X2") (pin "2") (pinfunction "CANL_2") (pintype "passive"))
    )
    (net (code "43") (name "Net-(X6-2)") (class "Default")
      (node (ref "SJ2") (pin "1") (pinfunction "1_1") (pintype "passive"))
      (node (ref "X6") (pin "P$2") (pinfunction "2_P$2") (pintype "bidirectional"))
      (node (ref "X7") (pin "P$2") (pinfunction "2_P$2") (pintype "bidirectional"))
    )
    (net (code "44") (name "Net-(X9-3)") (class "Default")
      (node (ref "R14") (pin "2") (pinfunction "2_2") (pintype "passive"))
      (node (ref "R15") (pin "2") (pinfunction "2_2") (pintype "passive"))
      (node (ref "X9") (pin "P$3") (pinfunction "3_P$3") (pintype "bidirectional"))
    )
    (net (code "45") (name "Q_NFLT") (class "Default")
      (node (ref "CANIO_1") (pin "PB1") (pinfunction "PB1_PB1") (pintype "bidirectional"))
      (node (ref "IC5") (pin "4") (pinfunction "ST1/2_4") (pintype "input"))
      (node (ref "IC5") (pin "8") (pinfunction "ST3/4_8") (pintype "input"))
      (node (ref "R11") (pin "1") (pinfunction "1_1") (pintype "passive"))
    )
    (net (code "46") (name "TS1") (class "Default")
      (node (ref "C12") (pin "2") (pinfunction "2_2") (pintype "passive"))
      (node (ref "CANIO_1") (pin "PA4") (pinfunction "PA4_PA4") (pintype "bidirectional"))
      (node (ref "R10") (pin "1") (pinfunction "1_1") (pintype "passive"))
      (node (ref "R9") (pin "2") (pinfunction "2_2") (pintype "passive"))
      (node (ref "ZD6") (pin "P$2") (pinfunction "P$2_P$2") (pintype "bidirectional"))
    )
    (net (code "47") (name "TS2") (class "Default")
      (node (ref "C11") (pin "2") (pinfunction "2_2") (pintype "passive"))
      (node (ref "CANIO_1") (pin "PA5") (pinfunction "PA5_PA5") (pintype "bidirectional"))
      (node (ref "R7") (pin "2") (pinfunction "2_2") (pintype "passive"))
      (node (ref "R8") (pin "1") (pinfunction "1_1") (pintype "passive"))
      (node (ref "ZD5") (pin "P$2") (pinfunction "P$2_P$2") (pintype "bidirectional"))
    )
    (net (code "48") (name "VBAT") (class "Default")
      (node (ref "C10") (pin "1") (pinfunction "1_1") (pintype "passive"))
      (node (ref "D1") (pin "C") (pinfunction "C_C") (pintype "passive"))
      (node (ref "IC4") (pin "2") (pinfunction "VIN_2") (pintype "passive"))
      (node (ref "IC5") (pin "1") (pinfunction "VBB_1") (pintype "power_in"))
      (node (ref "IC5") (pin "10") (pinfunction "VBB_10") (pintype "power_in"))
      (node (ref "IC5") (pin "11") (pinfunction "VBB_11") (pintype "power_in"))
      (node (ref "IC5") (pin "12") (pinfunction "VBB_12") (pintype "power_in"))
      (node (ref "IC5") (pin "15") (pinfunction "VBB_15") (pintype "power_in"))
      (node (ref "IC5") (pin "16") (pinfunction "VBB_16") (pintype "power_in"))
      (node (ref "IC5") (pin "19") (pinfunction "VBB_19") (pintype "power_in"))
      (node (ref "IC5") (pin "20") (pinfunction "VBB_20") (pintype "power_in"))
      (node (ref "IC6") (pin "1") (pinfunction "VS_1") (pintype "bidirectional"))
      (node (ref "IC6") (pin "7") (pinfunction "INH_7") (pintype "bidirectional"))
      (node (ref "LED1") (pin "A") (pinfunction "A_A") (pintype "passive"))
      (node (ref "TB1") (pin "VIN") (pinfunction "VIN_VIN") (pintype "passive"))
      (node (ref "TB2") (pin "VIN") (pinfunction "VIN_VIN") (pintype "passive"))
      (node (ref "X1") (pin "2") (pinfunction "2_2") (pintype "passive"))
      (node (ref "X2") (pin "4") (pinfunction "V+_4") (pintype "passive"))
      (node (ref "X9") (pin "P$4") (pinfunction "4_P$4") (pintype "bidirectional"))
    )
    (net (code "49") (name "VREF_PTC_CH") (class "Default")
      (node (ref "C11") (pin "1") (pinfunction "1_1") (pintype "passive"))
      (node (ref "C12") (pin "1") (pinfunction "1_1") (pintype "passive"))
      (node (ref "C13") (pin "1") (pinfunction "1_1") (pintype "passive"))
      (node (ref "CON1") (pin "2") (pinfunction "2_2") (pintype "passive"))
      (node (ref "CON2") (pin "2") (pinfunction "2_2") (pintype "passive"))
      (node (ref "IC4") (pin "6") (pinfunction "VOUT_6") (pintype "bidirectional"))
    )
    (net (code "50") (name "unconnected-(CANIO_1-PadAREF)") (class "Default")
      (node (ref "CANIO_1") (pin "AREF") (pinfunction "AREF_AREF") (pintype "output"))
    )
    (net (code "51") (name "unconnected-(IC4-~{SHDN}-Pad3)") (class "Default")
      (node (ref "IC4") (pin "3") (pinfunction "~{SHDN}_3") (pintype "passive"))
    )
  )
)
